# Power.net
KiCad netlist of a schematic drawn in Altium Designer
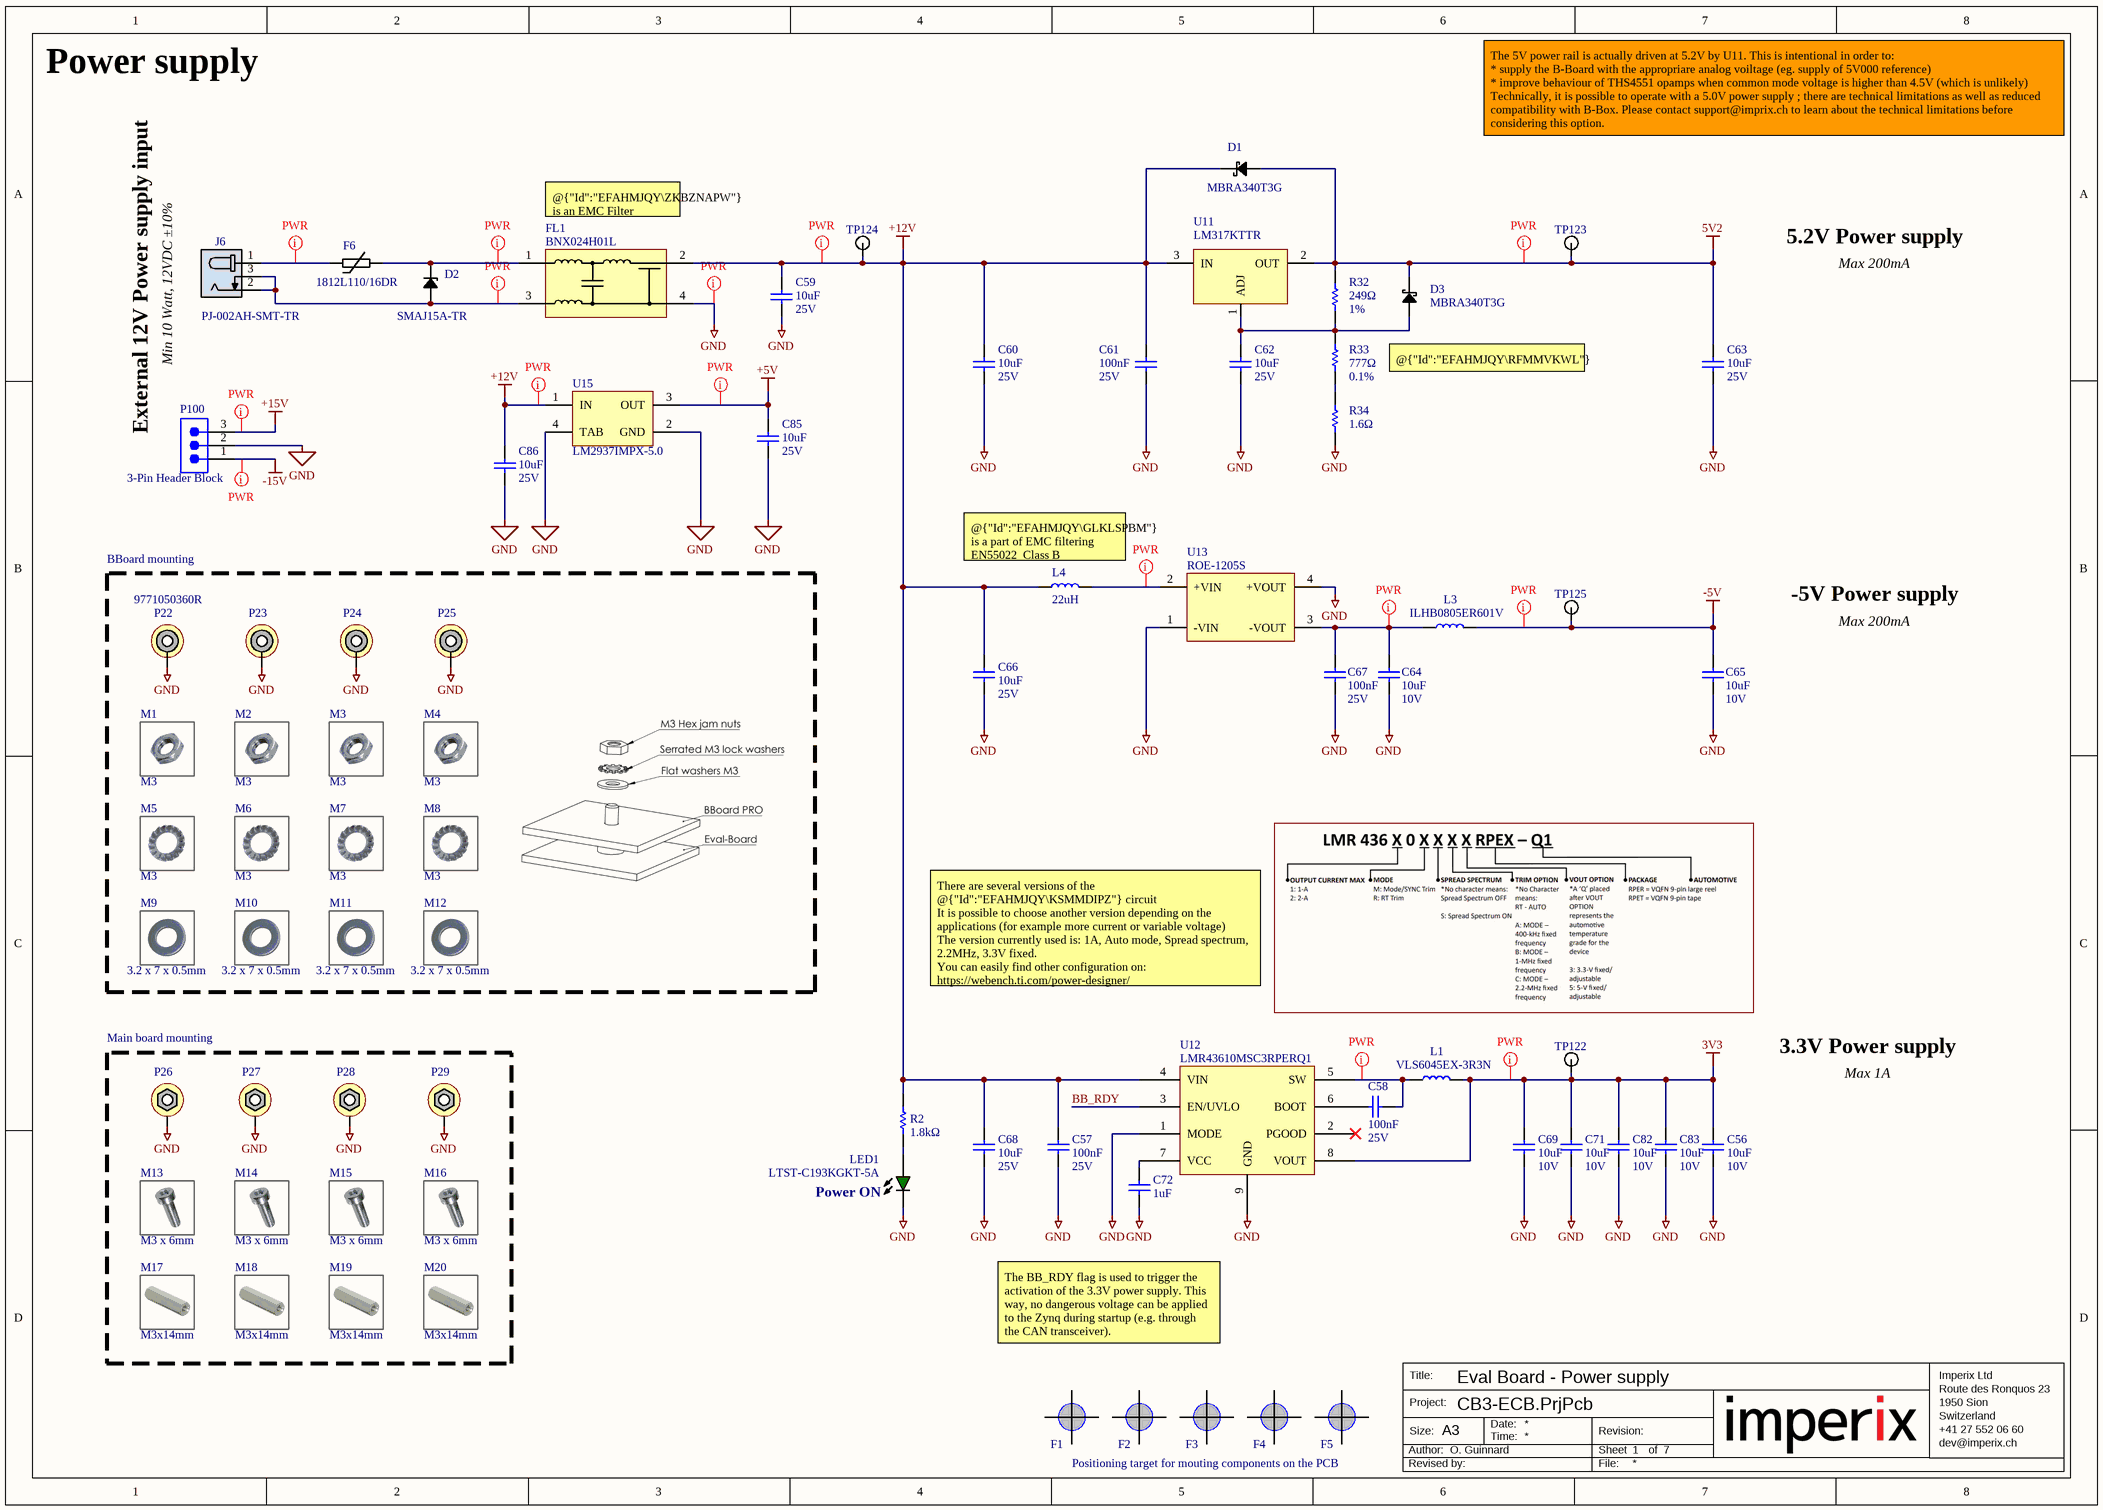
[diagram p0: Power.SchDoc]

(export (version "E")
  (design (tool "Eeschema 10.0.6"))
  (components
    (comp (ref "C56")
      (value "10uF")
      (footprint "CAPC1608L(0603)")
      (description "CAP CER 10UF 10V X5R 0603 10% (Generic Imperix Component)")
      (fields
        (field (name "TOLERANCE") "10%")
        (field (name "VOLTAGE RATING (DC)") "10V")
        (field (name "Comment") "CAP-10UF-10V-X5R-0603-10%")
      )
      (libsource (lib "CB3-ECB") (part "Capacitor non-polarized"))
    )
    (comp (ref "C57")
      (value "100nF")
      (footprint "CAPC1005L(0402)")
      (description "CAP CER 100NF 25V X7R 0402 10% (Generic Imperix Component)")
      (fields
        (field (name "TOLERANCE") "10%")
        (field (name "VOLTAGE RATING (DC)") "25V")
        (field (name "Comment") "CAP-100NF-25V-X7R-0402-10%")
      )
      (libsource (lib "CB3-ECB") (part "Capacitor non-polarized"))
    )
    (comp (ref "C58")
      (value "100nF")
      (footprint "CAPC1005L(0402)")
      (description "CAP CER 100NF 25V X7R 0402 10% (Generic Imperix Component)")
      (fields
        (field (name "TOLERANCE") "10%")
        (field (name "VOLTAGE RATING (DC)") "25V")
        (field (name "Comment") "CAP-100NF-25V-X7R-0402-10%")
      )
      (libsource (lib "CB3-ECB") (part "Capacitor non-polarized"))
    )
    (comp (ref "C59")
      (value "10uF")
      (footprint "CAPC3216L(1206)")
      (description "CAP CER 10UF 25V X5R 1206 10% (Generic Imperix Component)")
      (fields
        (field (name "TOLERANCE") "10%")
        (field (name "VOLTAGE RATING (DC)") "25V")
        (field (name "Comment") "CAP-10UF-25V-X5R-1206-10%")
      )
      (libsource (lib "CB3-ECB") (part "Capacitor non-polarized"))
    )
    (comp (ref "C60")
      (value "10uF")
      (footprint "CAPC3216L(1206)")
      (description "CAP CER 10UF 25V X5R 1206 10% (Generic Imperix Component)")
      (fields
        (field (name "TOLERANCE") "10%")
        (field (name "VOLTAGE RATING (DC)") "25V")
        (field (name "Comment") "CAP-10UF-25V-X5R-1206-10%")
      )
      (libsource (lib "CB3-ECB") (part "Capacitor non-polarized"))
    )
    (comp (ref "C61")
      (value "100nF")
      (footprint "CAPC1005L(0402)")
      (description "CAP CER 100NF 25V X7R 0402 10% (Generic Imperix Component)")
      (fields
        (field (name "TOLERANCE") "10%")
        (field (name "VOLTAGE RATING (DC)") "25V")
        (field (name "Comment") "CAP-100NF-25V-X7R-0402-10%")
      )
      (libsource (lib "CB3-ECB") (part "Capacitor non-polarized"))
    )
    (comp (ref "C62")
      (value "10uF")
      (footprint "CAPC3216L(1206)")
      (description "CAP CER 10UF 25V X5R 1206 10% (Generic Imperix Component)")
      (fields
        (field (name "TOLERANCE") "10%")
        (field (name "VOLTAGE RATING (DC)") "25V")
        (field (name "Comment") "CAP-10UF-25V-X5R-1206-10%")
      )
      (libsource (lib "CB3-ECB") (part "Capacitor non-polarized"))
    )
    (comp (ref "C63")
      (value "10uF")
      (footprint "CAPC3216L(1206)")
      (description "CAP CER 10UF 25V X5R 1206 10% (Generic Imperix Component)")
      (fields
        (field (name "TOLERANCE") "10%")
        (field (name "VOLTAGE RATING (DC)") "25V")
        (field (name "Comment") "CAP-10UF-25V-X5R-1206-10%")
      )
      (libsource (lib "CB3-ECB") (part "Capacitor non-polarized"))
    )
    (comp (ref "C64")
      (value "10uF")
      (footprint "CAPC1608L(0603)")
      (description "CAP CER 10UF 10V X5R 0603 10% (Generic Imperix Component)")
      (fields
        (field (name "TOLERANCE") "10%")
        (field (name "VOLTAGE RATING (DC)") "10V")
        (field (name "Comment") "CAP-10UF-10V-X5R-0603-10%")
      )
      (libsource (lib "CB3-ECB") (part "Capacitor non-polarized"))
    )
    (comp (ref "C65")
      (value "10uF")
      (footprint "CAPC1608L(0603)")
      (description "CAP CER 10UF 10V X5R 0603 10% (Generic Imperix Component)")
      (fields
        (field (name "TOLERANCE") "10%")
        (field (name "VOLTAGE RATING (DC)") "10V")
        (field (name "Comment") "CAP-10UF-10V-X5R-0603-10%")
      )
      (libsource (lib "CB3-ECB") (part "Capacitor non-polarized"))
    )
    (comp (ref "C66")
      (value "10uF")
      (footprint "CAPC3216L(1206)")
      (description "CAP CER 10UF 25V X5R 1206 10% (Generic Imperix Component)")
      (fields
        (field (name "TOLERANCE") "10%")
        (field (name "VOLTAGE RATING (DC)") "25V")
        (field (name "Comment") "CAP-10UF-25V-X5R-1206-10%")
      )
      (libsource (lib "CB3-ECB") (part "Capacitor non-polarized"))
    )
    (comp (ref "C67")
      (value "100nF")
      (footprint "CAPC1005L(0402)")
      (description "CAP CER 100NF 25V X7R 0402 10% (Generic Imperix Component)")
      (fields
        (field (name "TOLERANCE") "10%")
        (field (name "VOLTAGE RATING (DC)") "25V")
        (field (name "Comment") "CAP-100NF-25V-X7R-0402-10%")
      )
      (libsource (lib "CB3-ECB") (part "Capacitor non-polarized"))
    )
    (comp (ref "C68")
      (value "10uF")
      (footprint "CAPC3216L(1206)")
      (description "CAP CER 10UF 25V X5R 1206 10% (Generic Imperix Component)")
      (fields
        (field (name "TOLERANCE") "10%")
        (field (name "VOLTAGE RATING (DC)") "25V")
        (field (name "Comment") "CAP-10UF-25V-X5R-1206-10%")
      )
      (libsource (lib "CB3-ECB") (part "Capacitor non-polarized"))
    )
    (comp (ref "C69")
      (value "10uF")
      (footprint "CAPC1608L(0603)")
      (description "CAP CER 10UF 10V X5R 0603 10% (Generic Imperix Component)")
      (fields
        (field (name "TOLERANCE") "10%")
        (field (name "VOLTAGE RATING (DC)") "10V")
        (field (name "Comment") "CAP-10UF-10V-X5R-0603-10%")
      )
      (libsource (lib "CB3-ECB") (part "Capacitor non-polarized"))
    )
    (comp (ref "C71")
      (value "10uF")
      (footprint "CAPC1608L(0603)")
      (description "CAP CER 10UF 10V X5R 0603 10% (Generic Imperix Component)")
      (fields
        (field (name "TOLERANCE") "10%")
        (field (name "VOLTAGE RATING (DC)") "10V")
        (field (name "Comment") "CAP-10UF-10V-X5R-0603-10%")
      )
      (libsource (lib "CB3-ECB") (part "Capacitor non-polarized"))
    )
    (comp (ref "C72")
      (value "1uF")
      (footprint "CAPC1005L(0402)")
      (description "CAP CER 1UF 6.3V X5R 0402 5% (Generic Imperix Component)")
      (fields (field (name "TOLERANCE") "5%") (field (name "Comment") "CAP-1UF-6.3V-X5R-0402-5%"))
      (libsource (lib "CB3-ECB") (part "Capacitor non-polarized"))
    )
    (comp (ref "C82")
      (value "10uF")
      (footprint "CAPC1608L(0603)")
      (description "CAP CER 10UF 10V X5R 0603 10% (Generic Imperix Component)")
      (fields
        (field (name "TOLERANCE") "10%")
        (field (name "VOLTAGE RATING (DC)") "10V")
        (field (name "Comment") "CAP-10UF-10V-X5R-0603-10%")
      )
      (libsource (lib "CB3-ECB") (part "Capacitor non-polarized"))
    )
    (comp (ref "C83")
      (value "10uF")
      (footprint "CAPC1608L(0603)")
      (description "CAP CER 10UF 10V X5R 0603 10% (Generic Imperix Component)")
      (fields
        (field (name "TOLERANCE") "10%")
        (field (name "VOLTAGE RATING (DC)") "10V")
        (field (name "Comment") "CAP-10UF-10V-X5R-0603-10%")
      )
      (libsource (lib "CB3-ECB") (part "Capacitor non-polarized"))
    )
    (comp (ref "C85")
      (value "10uF")
      (footprint "CAPC3216L(1206)")
      (description "CAP CER 10UF 25V X5R 1206 10% (Generic Imperix Component)")
      (fields
        (field (name "TOLERANCE") "10%")
        (field (name "VOLTAGE RATING (DC)") "25V")
        (field (name "Comment") "CAP-10UF-25V-X5R-1206-10%")
      )
      (libsource (lib "CB3-ECB") (part "Capacitor non-polarized"))
    )
    (comp (ref "C86")
      (value "10uF")
      (footprint "CAPC3216L(1206)")
      (description "CAP CER 10UF 25V X5R 1206 10% (Generic Imperix Component)")
      (fields
        (field (name "TOLERANCE") "10%")
        (field (name "VOLTAGE RATING (DC)") "25V")
        (field (name "Comment") "CAP-10UF-25V-X5R-1206-10%")
      )
      (libsource (lib "CB3-ECB") (part "Capacitor non-polarized"))
    )
    (comp (ref "D1")
      (value "MBRA340T3G")
      (footprint "DO-214AC")
      (description "Diode Schottky 40 V 3A Surface Mount SMA")
      (libsource (lib "CB3-ECB") (part "Diode Schottky"))
    )
    (comp (ref "D2")
      (value "SMAJ15A-TR")
      (footprint "DO-214AC")
      (description "32.5V Clamp 71A (8/20µs) Ipp Tvs Diode Surface Mount SMA (DO-214AC) Unidirectional")
      (libsource (lib "CB3-ECB") (part "Diode TVS Unidirectional"))
    )
    (comp (ref "D3")
      (value "MBRA340T3G")
      (footprint "DO-214AC")
      (description "Diode Schottky 40 V 3A Surface Mount SMA")
      (libsource (lib "CB3-ECB") (part "Diode Schottky"))
    )
    (comp (ref "F1")
      (value "Fiducial")
      (footprint "Fiducial050")
      (description "Fiducial for pick&place (No BOM)")
      (libsource (lib "CB3-ECB") (part "Fiducial"))
    )
    (comp (ref "F2")
      (value "Fiducial")
      (footprint "Fiducial050")
      (description "Fiducial for pick&place (No BOM)")
      (libsource (lib "CB3-ECB") (part "Fiducial"))
    )
    (comp (ref "F3")
      (value "Fiducial")
      (footprint "Fiducial050")
      (description "Fiducial for pick&place (No BOM)")
      (libsource (lib "CB3-ECB") (part "Fiducial"))
    )
    (comp (ref "F4")
      (value "Fiducial")
      (footprint "Fiducial050")
      (description "Fiducial for pick&place (No BOM)")
      (libsource (lib "CB3-ECB") (part "Fiducial"))
    )
    (comp (ref "F5")
      (value "Fiducial")
      (footprint "Fiducial050")
      (description "Fiducial for pick&place (No BOM)")
      (libsource (lib "CB3-ECB") (part "Fiducial"))
    )
    (comp (ref "F6")
      (value "1812L110/16DR")
      (footprint "PTC Fuse(1812)")
      (description "PTC Resettable Fuse 1.1A(hold)  1.95A(trip) 16VDC 1812")
      (libsource (lib "CB3-ECB") (part "Resettable PTC fuse"))
    )
    (comp (ref "FL1")
      (value "BNX024H01L")
      (footprint "FP-BNX02-MFG")
      (description "EMI Filter Block 15A 50VDC Flat Style SMD Automotive Embossed T/R")
      (libsource (lib "CB3-ECB") (part "EMI Filter"))
    )
    (comp (ref "J6")
      (value "PJ-002AH-SMT-TR")
      (footprint "PJ-002AH-SMT-TR")
      (description "2.0 x 6.5 mm, 5.0 A, Horizontal, Surface Mount (SMT), Dc Power Jack Connector")
      (libsource (lib "CB3-ECB") (part "Connector Power Barrel"))
    )
    (comp (ref "L1")
      (value "VLS6045EX-3R3N")
      (footprint "VLS6045EX")
      (description "Inductor Power Shielded Wirewound 3.3uH 30% 100KHz Ferrite 4.95A 0.0299Ohm DCR 2424 T/R")
      (fields (field (name "TOLERANCE") "30%"))
      (libsource (lib "CB3-ECB") (part "Inductor"))
    )
    (comp (ref "L3")
      (value "ILHB0805ER601V")
      (footprint "RESC2012L(0805)")
      (description "Ferrite Beads Multi-Layer High Current 600Ohm 25% 100MHz 2A 100mOhm DCR 0805 T/R")
      (fields (field (name "TOLERANCE") "25%"))
      (libsource (lib "CB3-ECB") (part "Inductor"))
    )
    (comp (ref "L4")
      (value "22uH")
      (footprint "Inductor 8400 Serie")
      (description "Inductor Power Wirewound 22uH 10% 0.6A 0.6Ohm DCR 1812")
      (fields (field (name "TOLERANCE") "10%") (field (name "Comment") "84223C"))
      (libsource (lib "CB3-ECB") (part "Inductor"))
    )
    (comp (ref "LED1")
      (value "LTST-C193KGKT-5A")
      (footprint "LED0603_GREEN")
      (description "LED GREEN CLEAR 0603 SMD")
      (libsource (lib "CB3-ECB") (part "LED GREEN"))
    )
    (comp (ref "M1")
      (value "M3")
      (description "M3 Hex jam nuts")
      (fields (field (name "Comment") "1090615"))
      (libsource (lib "CB3-ECB") (part "1090615"))
    )
    (comp (ref "M2")
      (value "M3")
      (description "M3 Hex jam nuts")
      (fields (field (name "Comment") "1090615"))
      (libsource (lib "CB3-ECB") (part "1090615"))
    )
    (comp (ref "M3")
      (value "M3")
      (description "M3 Hex jam nuts")
      (fields (field (name "Comment") "1090615"))
      (libsource (lib "CB3-ECB") (part "1090615"))
    )
    (comp (ref "M4")
      (value "M3")
      (description "M3 Hex jam nuts")
      (fields (field (name "Comment") "1090615"))
      (libsource (lib "CB3-ECB") (part "1090615"))
    )
    (comp (ref "M5")
      (value "M3")
      (description "Serrated M3 lock washers type A, external serrations")
      (fields (field (name "Comment") "1278037"))
      (libsource (lib "CB3-ECB") (part "1278037"))
    )
    (comp (ref "M6")
      (value "M3")
      (description "Serrated M3 lock washers type A, external serrations")
      (fields (field (name "Comment") "1278037"))
      (libsource (lib "CB3-ECB") (part "1278037"))
    )
    (comp (ref "M7")
      (value "M3")
      (description "Serrated M3 lock washers type A, external serrations")
      (fields (field (name "Comment") "1278037"))
      (libsource (lib "CB3-ECB") (part "1278037"))
    )
    (comp (ref "M8")
      (value "M3")
      (description "Serrated M3 lock washers type A, external serrations")
      (fields (field (name "Comment") "1278037"))
      (libsource (lib "CB3-ECB") (part "1278037"))
    )
    (comp (ref "M9")
      (value "3.2 x 7 x 0.5mm")
      (description "Flat washers M3 without chamfer")
      (fields (field (name "Comment") "1887467"))
      (libsource (lib "CB3-ECB") (part "1887467"))
    )
    (comp (ref "M10")
      (value "3.2 x 7 x 0.5mm")
      (description "Flat washers M3 without chamfer")
      (fields (field (name "Comment") "1887467"))
      (libsource (lib "CB3-ECB") (part "1887467"))
    )
    (comp (ref "M11")
      (value "3.2 x 7 x 0.5mm")
      (description "Flat washers M3 without chamfer")
      (fields (field (name "Comment") "1887467"))
      (libsource (lib "CB3-ECB") (part "1887467"))
    )
    (comp (ref "M12")
      (value "3.2 x 7 x 0.5mm")
      (description "Flat washers M3 without chamfer")
      (fields (field (name "Comment") "1887467"))
      (libsource (lib "CB3-ECB") (part "1887467"))
    )
    (comp (ref "M13")
      (value "M3 x 6mm")
      (description "Hexalobular (6 Lobe) socket head cap M3x6mm screws with low head, fully threaded")
      (fields (field (name "Comment") "1145924"))
      (libsource (lib "CB3-ECB") (part "3645891"))
    )
    (comp (ref "M14")
      (value "M3 x 6mm")
      (description "Hexalobular (6 Lobe) socket head cap M3x6mm screws with low head, fully threaded")
      (fields (field (name "Comment") "1145924"))
      (libsource (lib "CB3-ECB") (part "3645891"))
    )
    (comp (ref "M15")
      (value "M3 x 6mm")
      (description "Hexalobular (6 Lobe) socket head cap M3x6mm screws with low head, fully threaded")
      (fields (field (name "Comment") "1145924"))
      (libsource (lib "CB3-ECB") (part "3645891"))
    )
    (comp (ref "M16")
      (value "M3 x 6mm")
      (description "Hexalobular (6 Lobe) socket head cap M3x6mm screws with low head, fully threaded")
      (fields (field (name "Comment") "1145924"))
      (libsource (lib "CB3-ECB") (part "3645891"))
    )
    (comp (ref "M17")
      (value "M3x14mm")
      (description "Brass Spacer M3x14mm  Metric Thread int./int.")
      (fields (field (name "Comment") "1382748"))
      (libsource (lib "CB3-ECB") (part "970200354"))
    )
    (comp (ref "M18")
      (value "M3x14mm")
      (description "Brass Spacer M3x14mm  Metric Thread int./int.")
      (fields (field (name "Comment") "1382748"))
      (libsource (lib "CB3-ECB") (part "970200354"))
    )
    (comp (ref "M19")
      (value "M3x14mm")
      (description "Brass Spacer M3x14mm  Metric Thread int./int.")
      (fields (field (name "Comment") "1382748"))
      (libsource (lib "CB3-ECB") (part "970200354"))
    )
    (comp (ref "M20")
      (value "M3x14mm")
      (description "Brass Spacer M3x14mm  Metric Thread int./int.")
      (fields (field (name "Comment") "1382748"))
      (libsource (lib "CB3-ECB") (part "970200354"))
    )
    (comp (ref "P22")
      (value "9771050360R")
      (footprint "9771050360R")
      (description "WA-SMSE SMT Steel Spacer, M3x5mm Thread External")
      (libsource (lib "CB3-ECB") (part "SMD Steel spacer"))
    )
    (comp (ref "P23")
      (value "9771050360R")
      (footprint "9771050360R")
      (description "WA-SMSE SMT Steel Spacer, M3x5mm Thread External")
      (libsource (lib "CB3-ECB") (part "SMD Steel spacer"))
    )
    (comp (ref "P24")
      (value "9771050360R")
      (footprint "9771050360R")
      (description "WA-SMSE SMT Steel Spacer, M3x5mm Thread External")
      (libsource (lib "CB3-ECB") (part "SMD Steel spacer"))
    )
    (comp (ref "P25")
      (value "9771050360R")
      (footprint "9771050360R")
      (description "WA-SMSE SMT Steel Spacer, M3x5mm Thread External")
      (libsource (lib "CB3-ECB") (part "SMD Steel spacer"))
    )
    (comp (ref "P26")
      (value "Spacer M3 connected")
      (footprint "Spacer M3 connected")
      (description "Hole and pad for spacer M3")
      (libsource (lib "CB3-ECB") (part "Spacer"))
    )
    (comp (ref "P27")
      (value "Spacer M3 connected")
      (footprint "Spacer M3 connected")
      (description "Hole and pad for spacer M3")
      (libsource (lib "CB3-ECB") (part "Spacer"))
    )
    (comp (ref "P28")
      (value "Spacer M3 connected")
      (footprint "Spacer M3 connected")
      (description "Hole and pad for spacer M3")
      (libsource (lib "CB3-ECB") (part "Spacer"))
    )
    (comp (ref "P29")
      (value "Spacer M3 connected")
      (footprint "Spacer M3 connected")
      (description "Hole and pad for spacer M3")
      (libsource (lib "CB3-ECB") (part "Spacer"))
    )
    (comp (ref "P100")
      (value "3-Pin Header Block")
      (footprint "691322310003")
      (description "TERM BLOCK HDR 3POS 90DEG 3.81MM")
      (fields (field (name "VOLTAGE") "300V") (field (name "MANUFACTURER") "Würth"))
      (libsource (lib "Altium Content Vault") (part "TBL - 1R - 03P - Male"))
    )
    (comp (ref "R2")
      (value "1.8kΩ")
      (footprint "RESC1608L(0603)")
      (description "RES SMD 1.8KΩ 1/8W 25PPM 0603 0.1% (Generic Imperix Component)")
      (fields (field (name "TOLERANCE") "0.1%") (field (name "Comment") "RES-1.8KΩ-1/8W-25PPM-0603-0.1%"))
      (libsource (lib "CB3-ECB") (part "Resistor"))
    )
    (comp (ref "R32")
      (value "249Ω")
      (footprint "RESC1005L(0402)")
      (description "RES SMD 249Ω 1/16W 100PPM 0402 1% (Generic Imperix Component)")
      (fields (field (name "TOLERANCE") "1%") (field (name "Comment") "RES-249Ω-1/16W-100PPM-0402-1%"))
      (libsource (lib "CB3-ECB") (part "Resistor"))
    )
    (comp (ref "R33")
      (value "777Ω")
      (footprint "RESC1005L(0402)")
      (description "RES SMD 777Ω 1/16W 25PPM 0402 0.1% (Generic Imperix Component)")
      (fields (field (name "TOLERANCE") "0.1%") (field (name "Comment") "RES-777Ω-1/16W-25PPM-0402-0.1%"))
      (libsource (lib "CB3-ECB") (part "Resistor"))
    )
    (comp (ref "R34")
      (value "1.6Ω")
      (footprint "RESC1005L(0402)")
      (description "RES SMD 1.6Ω 1/16WW 200PPM 0402 5% (Generic Imperix Component)")
      (fields (field (name "TOLERANCE") "5%") (field (name "Comment") "RES-1.6Ω-1/16WW-200PPM-0402-5%"))
      (libsource (lib "CB3-ECB") (part "Resistor"))
    )
    (comp (ref "TP122")
      (value "5001")
      (footprint "5001")
      (description "Black PC Test Point, Miniature Phosphor Bronze Silver Plating Through Hole Mounting Type")
      (libsource (lib "CB3-ECB") (part "Testpoint"))
    )
    (comp (ref "TP123")
      (value "5001")
      (footprint "5001")
      (description "Black PC Test Point, Miniature Phosphor Bronze Silver Plating Through Hole Mounting Type")
      (libsource (lib "CB3-ECB") (part "Testpoint"))
    )
    (comp (ref "TP124")
      (value "5001")
      (footprint "5001")
      (description "Black PC Test Point, Miniature Phosphor Bronze Silver Plating Through Hole Mounting Type")
      (libsource (lib "CB3-ECB") (part "Testpoint"))
    )
    (comp (ref "TP125")
      (value "5001")
      (footprint "5001")
      (description "Black PC Test Point, Miniature Phosphor Bronze Silver Plating Through Hole Mounting Type")
      (libsource (lib "CB3-ECB") (part "Testpoint"))
    )
    (comp (ref "U11")
      (value "LM317KTTR")
      (footprint "TO263-3")
      (description "IC REG LINEAR ADJ 1.5A DDPAK")
      (libsource (lib "CB3-ECB") (part "LM317KTTR"))
    )
    (comp (ref "U12")
      (value "LMR43610MSC3RPERQ1")
      (footprint "LMR43610MSC3RPERQ1")
      (description "LMR436x0, 36-V, 1-A Buck Converter")
      (libsource (lib "CB3-ECB") (part "LMR43610MSC3RPERQ1"))
    )
    (comp (ref "U13")
      (value "ROE-1205S")
      (footprint "ROE")
      (description "Isolated Module DC DC Converter 1 Output 5V 200mA 10.8V - 13.2V Input")
      (libsource (lib "CB3-ECB") (part "ROE"))
    )
    (comp (ref "U15")
      (value "LM2937IMPX-5.0")
      (footprint "MP04A_M")
      (description "IC REG LINEAR 5V 400MA SOT223-4")
      (libsource (lib "Technische Universität Darmstadt -  Institut für Stromrichtertechnik und Antriebsregelung") (part "PM-REG-LM2940-TO4"))
    )
  )
  (nets
    (net (code "1") (name "+5V") (class "Default")
      (node (ref "C85") (pin "2") (pinfunction "2_2") (pintype "passive"))
      (node (ref "U15") (pin "3") (pinfunction "OUT_3") (pintype "power_in"))
    )
    (net (code "2") (name "+12V") (class "Default")
      (node (ref "C57") (pin "2") (pinfunction "2_2") (pintype "passive"))
      (node (ref "C59") (pin "2") (pinfunction "2_2") (pintype "passive"))
      (node (ref "C60") (pin "2") (pinfunction "2_2") (pintype "passive"))
      (node (ref "C61") (pin "2") (pinfunction "2_2") (pintype "passive"))
      (node (ref "C66") (pin "2") (pinfunction "2_2") (pintype "passive"))
      (node (ref "C68") (pin "2") (pinfunction "2_2") (pintype "passive"))
      (node (ref "C86") (pin "2") (pinfunction "2_2") (pintype "passive"))
      (node (ref "D1") (pin "K") (pinfunction "K_K") (pintype "passive"))
      (node (ref "FL1") (pin "2") (pinfunction "CB_2") (pintype "passive"))
      (node (ref "L4") (pin "1") (pinfunction "1_1") (pintype "passive"))
      (node (ref "R2") (pin "2") (pinfunction "2_2") (pintype "passive"))
      (node (ref "TP124") (pin "1") (pinfunction "TP_1") (pintype "passive"))
      (node (ref "U11") (pin "3") (pinfunction "IN_3") (pintype "passive"))
      (node (ref "U12") (pin "4") (pinfunction "VIN_4") (pintype "passive"))
      (node (ref "U15") (pin "1") (pinfunction "IN_1") (pintype "power_in"))
    )
    (net (code "3") (name "+15V") (class "Default")
      (node (ref "P100") (pin "3") (pinfunction "3_3") (pintype "passive"))
    )
    (net (code "4") (name "-5V") (class "Default")
      (node (ref "C65") (pin "1") (pinfunction "1_1") (pintype "passive"))
      (node (ref "L3") (pin "2") (pinfunction "2_2") (pintype "passive"))
      (node (ref "TP125") (pin "1") (pinfunction "TP_1") (pintype "passive"))
    )
    (net (code "5") (name "-15V") (class "Default")
      (node (ref "P100") (pin "1") (pinfunction "1_1") (pintype "passive"))
    )
    (net (code "6") (name "/BB_RDY") (class "Default")
      (node (ref "U12") (pin "3") (pinfunction "EN/UVLO_3") (pintype "passive"))
    )
    (net (code "7") (name "3V3") (class "Default")
      (node (ref "C56") (pin "2") (pinfunction "2_2") (pintype "passive"))
      (node (ref "C69") (pin "2") (pinfunction "2_2") (pintype "passive"))
      (node (ref "C71") (pin "2") (pinfunction "2_2") (pintype "passive"))
      (node (ref "C82") (pin "2") (pinfunction "2_2") (pintype "passive"))
      (node (ref "C83") (pin "2") (pinfunction "2_2") (pintype "passive"))
      (node (ref "L1") (pin "2") (pinfunction "2_2") (pintype "passive"))
      (node (ref "TP122") (pin "1") (pinfunction "TP_1") (pintype "passive"))
      (node (ref "U12") (pin "8") (pinfunction "VOUT_8") (pintype "passive"))
    )
    (net (code "8") (name "5V2") (class "Default")
      (node (ref "C63") (pin "2") (pinfunction "2_2") (pintype "passive"))
      (node (ref "D1") (pin "A") (pinfunction "A_A") (pintype "passive"))
      (node (ref "D3") (pin "K") (pinfunction "K_K") (pintype "passive"))
      (node (ref "R32") (pin "2") (pinfunction "2_2") (pintype "passive"))
      (node (ref "TP123") (pin "1") (pinfunction "TP_1") (pintype "passive"))
      (node (ref "U11") (pin "2") (pinfunction "OUT_2") (pintype "passive"))
    )
    (net (code "9") (name "GND") (class "Default")
      (node (ref "C56") (pin "1") (pinfunction "1_1") (pintype "passive"))
      (node (ref "C57") (pin "1") (pinfunction "1_1") (pintype "passive"))
      (node (ref "C59") (pin "1") (pinfunction "1_1") (pintype "passive"))
      (node (ref "C60") (pin "1") (pinfunction "1_1") (pintype "passive"))
      (node (ref "C61") (pin "1") (pinfunction "1_1") (pintype "passive"))
      (node (ref "C62") (pin "1") (pinfunction "1_1") (pintype "passive"))
      (node (ref "C63") (pin "1") (pinfunction "1_1") (pintype "passive"))
      (node (ref "C64") (pin "2") (pinfunction "2_2") (pintype "passive"))
      (node (ref "C65") (pin "2") (pinfunction "2_2") (pintype "passive"))
      (node (ref "C66") (pin "1") (pinfunction "1_1") (pintype "passive"))
      (node (ref "C67") (pin "2") (pinfunction "2_2") (pintype "passive"))
      (node (ref "C68") (pin "1") (pinfunction "1_1") (pintype "passive"))
      (node (ref "C69") (pin "1") (pinfunction "1_1") (pintype "passive"))
      (node (ref "C71") (pin "1") (pinfunction "1_1") (pintype "passive"))
      (node (ref "C72") (pin "1") (pinfunction "1_1") (pintype "passive"))
      (node (ref "C82") (pin "1") (pinfunction "1_1") (pintype "passive"))
      (node (ref "C83") (pin "1") (pinfunction "1_1") (pintype "passive"))
      (node (ref "C85") (pin "1") (pinfunction "1_1") (pintype "passive"))
      (node (ref "C86") (pin "1") (pinfunction "1_1") (pintype "passive"))
      (node (ref "FL1") (pin "4") (pinfunction "CG_4") (pintype "passive"))
      (node (ref "LED1") (pin "K") (pinfunction "K_K") (pintype "passive"))
      (node (ref "P100") (pin "2") (pinfunction "2_2") (pintype "passive"))
      (node (ref "P22") (pin "0") (pinfunction "0_0") (pintype "passive"))
      (node (ref "P23") (pin "0") (pinfunction "0_0") (pintype "passive"))
      (node (ref "P24") (pin "0") (pinfunction "0_0") (pintype "passive"))
      (node (ref "P25") (pin "0") (pinfunction "0_0") (pintype "passive"))
      (node (ref "P26") (pin "1") (pinfunction "0_1") (pintype "passive"))
      (node (ref "P27") (pin "1") (pinfunction "0_1") (pintype "passive"))
      (node (ref "P28") (pin "1") (pinfunction "0_1") (pintype "passive"))
      (node (ref "P29") (pin "1") (pinfunction "0_1") (pintype "passive"))
      (node (ref "R34") (pin "1") (pinfunction "1_1") (pintype "passive"))
      (node (ref "U12") (pin "1") (pinfunction "MODE_1") (pintype "passive"))
      (node (ref "U12") (pin "9") (pinfunction "GND_9") (pintype "passive"))
      (node (ref "U13") (pin "1") (pinfunction "-VIN_1") (pintype "power_in"))
      (node (ref "U13") (pin "4") (pinfunction "+VOUT_4") (pintype "power_in"))
      (node (ref "U15") (pin "2") (pinfunction "GND_2") (pintype "power_in"))
      (node (ref "U15") (pin "4") (pinfunction "TAB_4") (pintype "power_in"))
    )
    (net (code "10") (name "Net-(F6-Pad1)") (class "Default")
      (node (ref "F6") (pin "1") (pinfunction "1_1") (pintype "passive"))
      (node (ref "J6") (pin "1") (pinfunction "1_1") (pintype "passive"))
    )
    (net (code "11") (name "Net-(FL1-B)") (class "Default")
      (node (ref "D2") (pin "K") (pinfunction "K_K") (pintype "passive"))
      (node (ref "F6") (pin "2") (pinfunction "2_2") (pintype "passive"))
      (node (ref "FL1") (pin "1") (pinfunction "B_1") (pintype "passive"))
    )
    (net (code "12") (name "Net-(FL1-PSG)") (class "Default")
      (node (ref "D2") (pin "A") (pinfunction "A_A") (pintype "passive"))
      (node (ref "FL1") (pin "3") (pinfunction "PSG_3") (pintype "passive"))
      (node (ref "J6") (pin "2") (pinfunction "2_2") (pintype "passive"))
      (node (ref "J6") (pin "3") (pinfunction "3_3") (pintype "passive"))
    )
    (net (code "13") (name "Net-(LED1-PadA)") (class "Default")
      (node (ref "LED1") (pin "A") (pinfunction "A_A") (pintype "passive"))
      (node (ref "R2") (pin "1") (pinfunction "1_1") (pintype "passive"))
    )
    (net (code "14") (name "Net-(R33-Pad1)") (class "Default")
      (node (ref "R33") (pin "1") (pinfunction "1_1") (pintype "passive"))
      (node (ref "R34") (pin "2") (pinfunction "2_2") (pintype "passive"))
    )
    (net (code "15") (name "Net-(U11-ADJ)") (class "Default")
      (node (ref "C62") (pin "2") (pinfunction "2_2") (pintype "passive"))
      (node (ref "D3") (pin "A") (pinfunction "A_A") (pintype "passive"))
      (node (ref "R32") (pin "1") (pinfunction "1_1") (pintype "passive"))
      (node (ref "R33") (pin "2") (pinfunction "2_2") (pintype "passive"))
      (node (ref "U11") (pin "1") (pinfunction "ADJ_1") (pintype "passive"))
    )
    (net (code "16") (name "Net-(U12-BOOT)") (class "Default")
      (node (ref "C58") (pin "2") (pinfunction "2_2") (pintype "passive"))
      (node (ref "U12") (pin "6") (pinfunction "BOOT_6") (pintype "passive"))
    )
    (net (code "17") (name "Net-(U12-SW)") (class "Default")
      (node (ref "C58") (pin "1") (pinfunction "1_1") (pintype "passive"))
      (node (ref "L1") (pin "1") (pinfunction "1_1") (pintype "passive"))
      (node (ref "U12") (pin "5") (pinfunction "SW_5") (pintype "passive"))
    )
    (net (code "18") (name "Net-(U12-VCC)") (class "Default")
      (node (ref "C72") (pin "2") (pinfunction "2_2") (pintype "passive"))
      (node (ref "U12") (pin "7") (pinfunction "VCC_7") (pintype "passive"))
    )
    (net (code "19") (name "Net-(U13-+VIN)") (class "Default")
      (node (ref "L4") (pin "2") (pinfunction "2_2") (pintype "passive"))
      (node (ref "U13") (pin "2") (pinfunction "+VIN_2") (pintype "power_in"))
    )
    (net (code "20") (name "Net-(U13--VOUT)") (class "Default")
      (node (ref "C64") (pin "1") (pinfunction "1_1") (pintype "passive"))
      (node (ref "C67") (pin "1") (pinfunction "1_1") (pintype "passive"))
      (node (ref "L3") (pin "1") (pinfunction "1_1") (pintype "passive"))
      (node (ref "U13") (pin "3") (pinfunction "-VOUT_3") (pintype "power_in"))
    )
    (net (code "21") (name "unconnected-(U12-PGOOD-Pad2)") (class "Default")
      (node (ref "U12") (pin "2") (pinfunction "PGOOD_2") (pintype "passive+no_connect"))
    )
  )
)
